# shield_motor.net
KiCad netlist of a schematic drawn in EAGLE
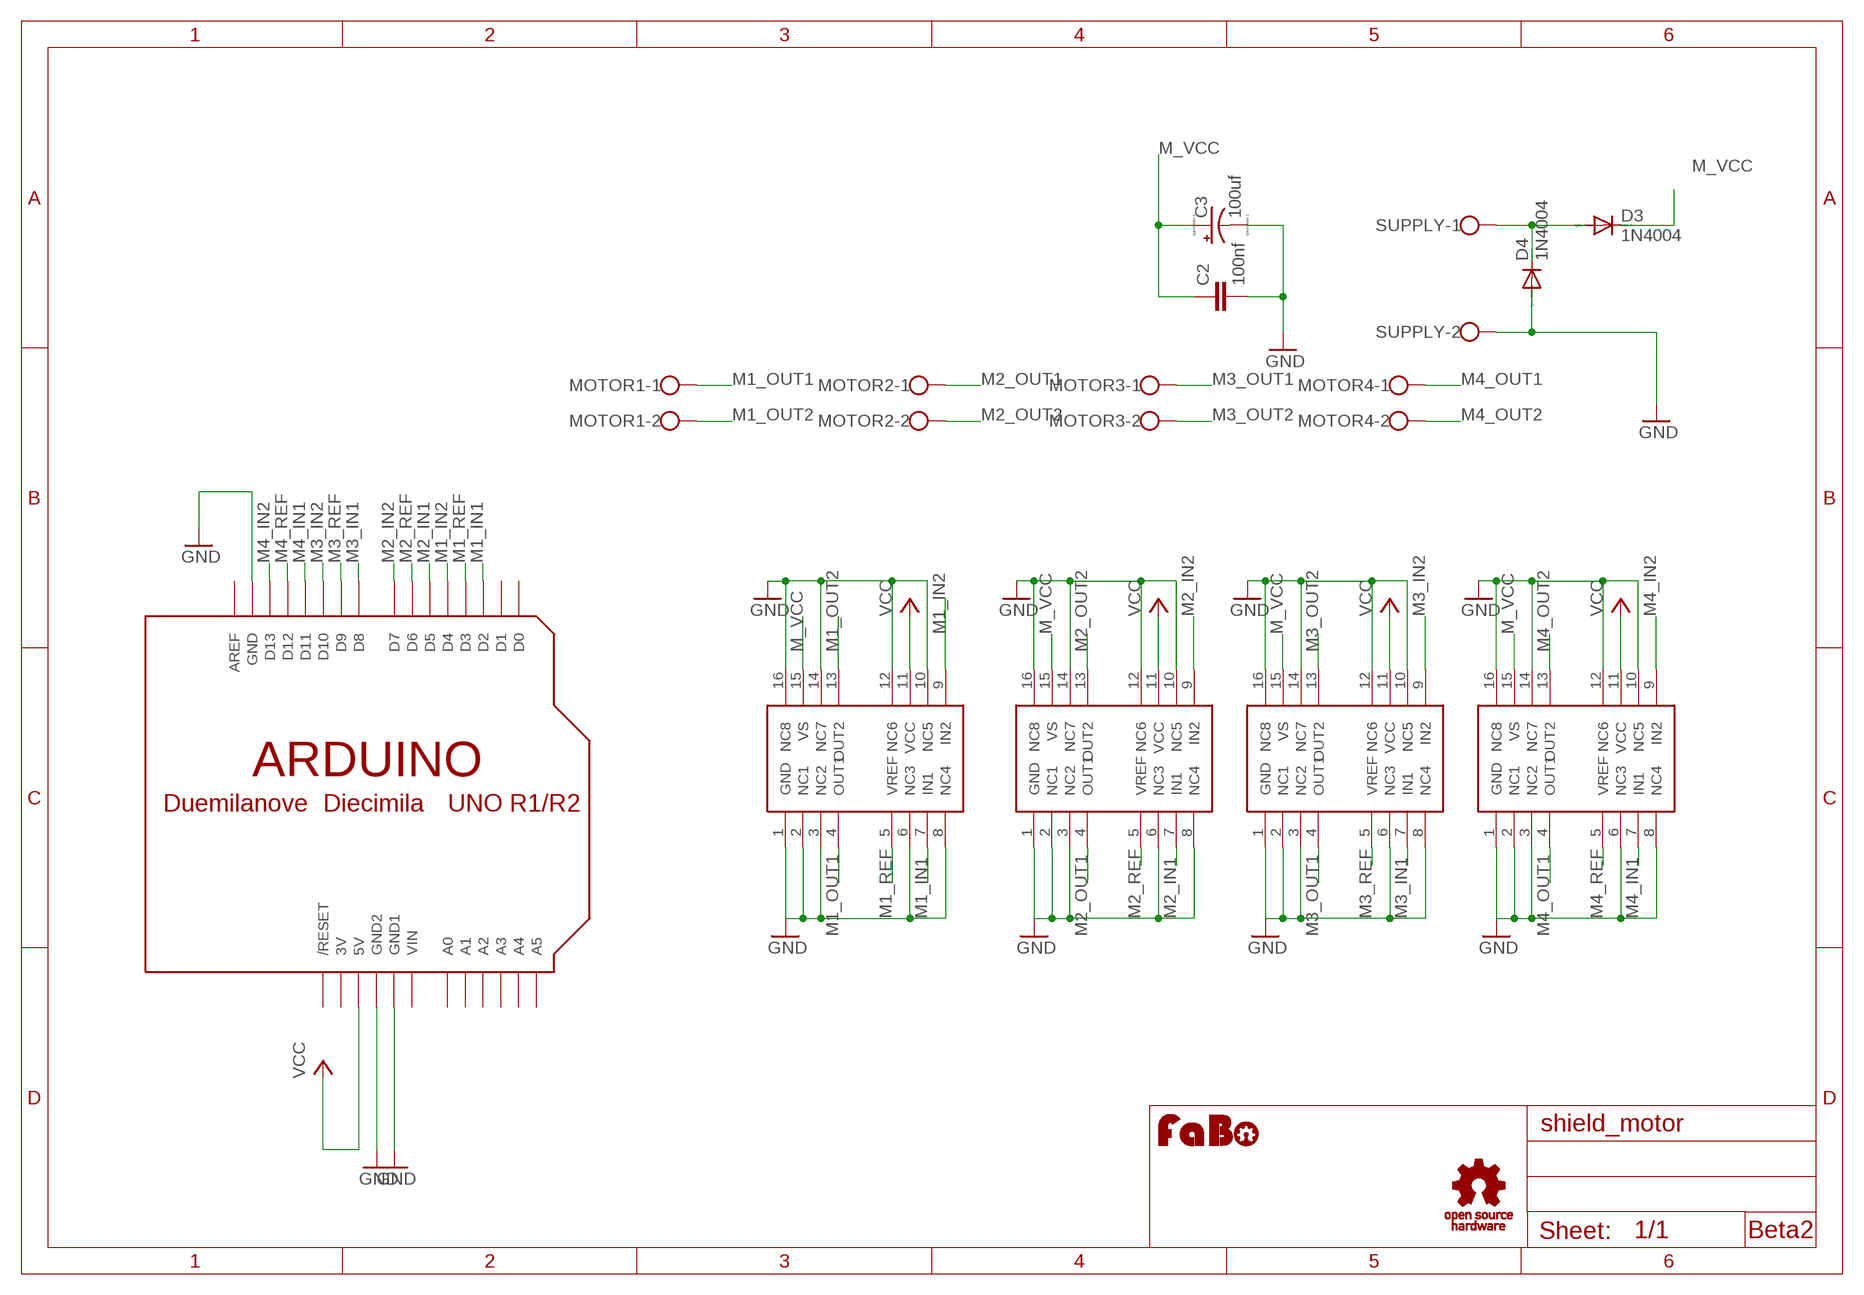
[diagram p0: schematic, sheet 1]

(export (version "E")
  (design (tool "Eeschema 10.0.6"))
  (components
    (comp (ref "C2")
      (value "100nf")
      (footprint "eagle-import:C0603")
      (libsource (lib "eagle-import") (part "C-EUC0603"))
    )
    (comp (ref "C3")
      (value "100uf")
      (footprint "eagle-import:153CLV-0405")
      (libsource (lib "eagle-import") (part "CPOL-US153CLV-0405"))
    )
    (comp (ref "D3")
      (value "1N4004")
      (footprint "eagle-import:DO41-10")
      (libsource (lib "eagle-import") (part "1N4004"))
    )
    (comp (ref "D4")
      (value "1N4004")
      (footprint "eagle-import:DO41-10")
      (libsource (lib "eagle-import") (part "1N4004"))
    )
    (comp (ref "MOTOR1")
      (value "W237-102")
      (footprint "eagle-import:W237-102")
      (fields (field (name "MPN") "237-102"))
      (libsource (lib "eagle-import") (part "W237-102"))
    )
    (comp (ref "MOTOR2")
      (value "W237-102")
      (footprint "eagle-import:W237-102")
      (fields (field (name "MPN") "237-102"))
      (libsource (lib "eagle-import") (part "W237-102"))
    )
    (comp (ref "MOTOR3")
      (value "W237-102")
      (footprint "eagle-import:W237-102")
      (fields (field (name "MPN") "237-102"))
      (libsource (lib "eagle-import") (part "W237-102"))
    )
    (comp (ref "MOTOR4")
      (value "W237-102")
      (footprint "eagle-import:W237-102")
      (fields (field (name "MPN") "237-102"))
      (libsource (lib "eagle-import") (part "W237-102"))
    )
    (comp (ref "SUPPLY")
      (value "W237-102")
      (footprint "eagle-import:W237-102")
      (fields (field (name "MPN") "237-102"))
      (libsource (lib "eagle-import") (part "W237-102"))
    )
    (comp (ref "U$1")
      (value "ARDUINO-NOHOLE")
      (footprint "eagle-import:ARDUINO-NOHOLE")
      (libsource (lib "eagle-import") (part "ARDUINO-NOHOLE"))
    )
    (comp (ref "U$2")
      (value "MOTOR-DRIVER-TA7281FG")
      (footprint "eagle-import:MOTOR-DRIVER-TA7291FG")
      (libsource (lib "eagle-import") (part "MOTOR-DRIVER-TA7281FG"))
    )
    (comp (ref "U$3")
      (value "MOTOR-DRIVER-TA7281FG")
      (footprint "eagle-import:MOTOR-DRIVER-TA7291FG")
      (libsource (lib "eagle-import") (part "MOTOR-DRIVER-TA7281FG"))
    )
    (comp (ref "U$4")
      (value "MOTOR-DRIVER-TA7281FG")
      (footprint "eagle-import:MOTOR-DRIVER-TA7291FG")
      (libsource (lib "eagle-import") (part "MOTOR-DRIVER-TA7281FG"))
    )
    (comp (ref "U$5")
      (value "MOTOR-DRIVER-TA7281FG")
      (footprint "eagle-import:MOTOR-DRIVER-TA7291FG")
      (libsource (lib "eagle-import") (part "MOTOR-DRIVER-TA7281FG"))
    )
    (comp (ref "U$7")
      (value "LOGO_FABO-M")
      (footprint "eagle-import:LOGO_FABO_M")
      (libsource (lib "eagle-import") (part "LOGO_FABO-M"))
    )
    (comp (ref "U$8")
      (value "LOGO_OSHW_T-M")
      (footprint "eagle-import:LOGO_OSHW_T_M")
      (libsource (lib "eagle-import") (part "LOGO_OSHW_T-M"))
    )
  )
  (nets
    (net (code "1") (name "/3V") (class "Default")
      (node (ref "U$1") (pin "3V") (pinfunction "3V_3V") (pintype "power_in"))
    )
    (net (code "2") (name "/M1_IN1") (class "Default")
      (node (ref "U$1") (pin "D2") (pinfunction "D2_D2") (pintype "bidirectional"))
      (node (ref "U$3") (pin "7") (pinfunction "IN1_7") (pintype "bidirectional"))
    )
    (net (code "3") (name "/M1_IN2") (class "Default")
      (node (ref "U$1") (pin "D4") (pinfunction "D4_D4") (pintype "bidirectional"))
      (node (ref "U$3") (pin "9") (pinfunction "IN2_9") (pintype "bidirectional"))
    )
    (net (code "4") (name "/M1_OUT1") (class "Default")
      (node (ref "MOTOR1") (pin "1") (pinfunction "KL_1") (pintype "passive"))
      (node (ref "U$3") (pin "4") (pinfunction "OUT1_4") (pintype "bidirectional"))
    )
    (net (code "5") (name "/M1_OUT2") (class "Default")
      (node (ref "MOTOR1") (pin "2") (pinfunction "KL_2") (pintype "passive"))
      (node (ref "U$3") (pin "13") (pinfunction "OUT2_13") (pintype "bidirectional"))
    )
    (net (code "6") (name "/M1_REF") (class "Default")
      (node (ref "U$1") (pin "D3") (pinfunction "D3_D3") (pintype "bidirectional"))
      (node (ref "U$3") (pin "5") (pinfunction "VREF_5") (pintype "bidirectional"))
    )
    (net (code "7") (name "/M2_IN1") (class "Default")
      (node (ref "U$1") (pin "D5") (pinfunction "D5_D5") (pintype "bidirectional"))
      (node (ref "U$4") (pin "7") (pinfunction "IN1_7") (pintype "bidirectional"))
    )
    (net (code "8") (name "/M2_IN2") (class "Default")
      (node (ref "U$1") (pin "D7") (pinfunction "D7_D7") (pintype "bidirectional"))
      (node (ref "U$4") (pin "9") (pinfunction "IN2_9") (pintype "bidirectional"))
    )
    (net (code "9") (name "/M2_OUT1") (class "Default")
      (node (ref "MOTOR2") (pin "1") (pinfunction "KL_1") (pintype "passive"))
      (node (ref "U$4") (pin "4") (pinfunction "OUT1_4") (pintype "bidirectional"))
    )
    (net (code "10") (name "/M2_OUT2") (class "Default")
      (node (ref "MOTOR2") (pin "2") (pinfunction "KL_2") (pintype "passive"))
      (node (ref "U$4") (pin "13") (pinfunction "OUT2_13") (pintype "bidirectional"))
    )
    (net (code "11") (name "/M2_REF") (class "Default")
      (node (ref "U$1") (pin "D6") (pinfunction "D6_D6") (pintype "bidirectional"))
      (node (ref "U$4") (pin "5") (pinfunction "VREF_5") (pintype "bidirectional"))
    )
    (net (code "12") (name "/M3_IN1") (class "Default")
      (node (ref "U$1") (pin "D8") (pinfunction "D8_D8") (pintype "bidirectional"))
      (node (ref "U$2") (pin "7") (pinfunction "IN1_7") (pintype "bidirectional"))
    )
    (net (code "13") (name "/M3_IN2") (class "Default")
      (node (ref "U$1") (pin "D10") (pinfunction "D10_D10") (pintype "bidirectional"))
      (node (ref "U$2") (pin "9") (pinfunction "IN2_9") (pintype "bidirectional"))
    )
    (net (code "14") (name "/M3_OUT1") (class "Default")
      (node (ref "MOTOR3") (pin "1") (pinfunction "KL_1") (pintype "passive"))
      (node (ref "U$2") (pin "4") (pinfunction "OUT1_4") (pintype "bidirectional"))
    )
    (net (code "15") (name "/M3_OUT2") (class "Default")
      (node (ref "MOTOR3") (pin "2") (pinfunction "KL_2") (pintype "passive"))
      (node (ref "U$2") (pin "13") (pinfunction "OUT2_13") (pintype "bidirectional"))
    )
    (net (code "16") (name "/M3_REF") (class "Default")
      (node (ref "U$1") (pin "D9") (pinfunction "D9_D9") (pintype "bidirectional"))
      (node (ref "U$2") (pin "5") (pinfunction "VREF_5") (pintype "bidirectional"))
    )
    (net (code "17") (name "/M4_IN1") (class "Default")
      (node (ref "U$1") (pin "D11") (pinfunction "D11_D11") (pintype "bidirectional"))
      (node (ref "U$5") (pin "7") (pinfunction "IN1_7") (pintype "bidirectional"))
    )
    (net (code "18") (name "/M4_IN2") (class "Default")
      (node (ref "U$1") (pin "D13") (pinfunction "D13_D13") (pintype "bidirectional"))
      (node (ref "U$5") (pin "9") (pinfunction "IN2_9") (pintype "bidirectional"))
    )
    (net (code "19") (name "/M4_OUT1") (class "Default")
      (node (ref "MOTOR4") (pin "1") (pinfunction "KL_1") (pintype "passive"))
      (node (ref "U$5") (pin "4") (pinfunction "OUT1_4") (pintype "bidirectional"))
    )
    (net (code "20") (name "/M4_OUT2") (class "Default")
      (node (ref "MOTOR4") (pin "2") (pinfunction "KL_2") (pintype "passive"))
      (node (ref "U$5") (pin "13") (pinfunction "OUT2_13") (pintype "bidirectional"))
    )
    (net (code "21") (name "/M4_REF") (class "Default")
      (node (ref "U$1") (pin "D12") (pinfunction "D12_D12") (pintype "bidirectional"))
      (node (ref "U$5") (pin "5") (pinfunction "VREF_5") (pintype "bidirectional"))
    )
    (net (code "22") (name "/M_VCC") (class "Default")
      (node (ref "C2") (pin "1") (pinfunction "1_1") (pintype "passive"))
      (node (ref "C3") (pin "+") (pinfunction "+_+") (pintype "passive"))
      (node (ref "D3") (pin "C") (pinfunction "C_C") (pintype "passive"))
      (node (ref "U$2") (pin "15") (pinfunction "VS_15") (pintype "bidirectional"))
      (node (ref "U$3") (pin "15") (pinfunction "VS_15") (pintype "bidirectional"))
      (node (ref "U$4") (pin "15") (pinfunction "VS_15") (pintype "bidirectional"))
      (node (ref "U$5") (pin "15") (pinfunction "VS_15") (pintype "bidirectional"))
    )
    (net (code "23") (name "/VIN") (class "Default")
      (node (ref "U$1") (pin "VIN") (pinfunction "VIN_VIN") (pintype "power_in"))
    )
    (net (code "24") (name "GND") (class "Default")
      (node (ref "C2") (pin "2") (pinfunction "2_2") (pintype "passive"))
      (node (ref "C3") (pin "-") (pinfunction "-_-") (pintype "passive"))
      (node (ref "D4") (pin "A") (pinfunction "A_A") (pintype "passive"))
      (node (ref "SUPPLY") (pin "2") (pinfunction "KL_2") (pintype "passive"))
      (node (ref "U$1") (pin "GND") (pinfunction "GND_GND") (pintype "power_in"))
      (node (ref "U$1") (pin "GND1") (pinfunction "GND1_GND1") (pintype "power_in"))
      (node (ref "U$1") (pin "GND2") (pinfunction "GND2_GND2") (pintype "power_in"))
      (node (ref "U$2") (pin "1") (pinfunction "GND_1") (pintype "bidirectional"))
      (node (ref "U$2") (pin "10") (pinfunction "NC5_10") (pintype "bidirectional"))
      (node (ref "U$2") (pin "12") (pinfunction "NC6_12") (pintype "bidirectional"))
      (node (ref "U$2") (pin "14") (pinfunction "NC7_14") (pintype "bidirectional"))
      (node (ref "U$2") (pin "16") (pinfunction "NC8_16") (pintype "bidirectional"))
      (node (ref "U$2") (pin "2") (pinfunction "NC1_2") (pintype "bidirectional"))
      (node (ref "U$2") (pin "3") (pinfunction "NC2_3") (pintype "bidirectional"))
      (node (ref "U$2") (pin "6") (pinfunction "NC3_6") (pintype "bidirectional"))
      (node (ref "U$2") (pin "8") (pinfunction "NC4_8") (pintype "bidirectional"))
      (node (ref "U$3") (pin "1") (pinfunction "GND_1") (pintype "bidirectional"))
      (node (ref "U$3") (pin "10") (pinfunction "NC5_10") (pintype "bidirectional"))
      (node (ref "U$3") (pin "12") (pinfunction "NC6_12") (pintype "bidirectional"))
      (node (ref "U$3") (pin "14") (pinfunction "NC7_14") (pintype "bidirectional"))
      (node (ref "U$3") (pin "16") (pinfunction "NC8_16") (pintype "bidirectional"))
      (node (ref "U$3") (pin "2") (pinfunction "NC1_2") (pintype "bidirectional"))
      (node (ref "U$3") (pin "3") (pinfunction "NC2_3") (pintype "bidirectional"))
      (node (ref "U$3") (pin "6") (pinfunction "NC3_6") (pintype "bidirectional"))
      (node (ref "U$3") (pin "8") (pinfunction "NC4_8") (pintype "bidirectional"))
      (node (ref "U$4") (pin "1") (pinfunction "GND_1") (pintype "bidirectional"))
      (node (ref "U$4") (pin "10") (pinfunction "NC5_10") (pintype "bidirectional"))
      (node (ref "U$4") (pin "12") (pinfunction "NC6_12") (pintype "bidirectional"))
      (node (ref "U$4") (pin "14") (pinfunction "NC7_14") (pintype "bidirectional"))
      (node (ref "U$4") (pin "16") (pinfunction "NC8_16") (pintype "bidirectional"))
      (node (ref "U$4") (pin "2") (pinfunction "NC1_2") (pintype "bidirectional"))
      (node (ref "U$4") (pin "3") (pinfunction "NC2_3") (pintype "bidirectional"))
      (node (ref "U$4") (pin "6") (pinfunction "NC3_6") (pintype "bidirectional"))
      (node (ref "U$4") (pin "8") (pinfunction "NC4_8") (pintype "bidirectional"))
      (node (ref "U$5") (pin "1") (pinfunction "GND_1") (pintype "bidirectional"))
      (node (ref "U$5") (pin "10") (pinfunction "NC5_10") (pintype "bidirectional"))
      (node (ref "U$5") (pin "12") (pinfunction "NC6_12") (pintype "bidirectional"))
      (node (ref "U$5") (pin "14") (pinfunction "NC7_14") (pintype "bidirectional"))
      (node (ref "U$5") (pin "16") (pinfunction "NC8_16") (pintype "bidirectional"))
      (node (ref "U$5") (pin "2") (pinfunction "NC1_2") (pintype "bidirectional"))
      (node (ref "U$5") (pin "3") (pinfunction "NC2_3") (pintype "bidirectional"))
      (node (ref "U$5") (pin "6") (pinfunction "NC3_6") (pintype "bidirectional"))
      (node (ref "U$5") (pin "8") (pinfunction "NC4_8") (pintype "bidirectional"))
    )
    (net (code "25") (name "Net-(SUPPLYA-KL)") (class "Default")
      (node (ref "D3") (pin "A") (pinfunction "A_A") (pintype "passive"))
      (node (ref "D4") (pin "C") (pinfunction "C_C") (pintype "passive"))
      (node (ref "SUPPLY") (pin "1") (pinfunction "KL_1") (pintype "passive"))
    )
    (net (code "26") (name "VCC") (class "Default")
      (node (ref "U$1") (pin "5V") (pinfunction "5V_5V") (pintype "power_in"))
      (node (ref "U$2") (pin "11") (pinfunction "VCC_11") (pintype "bidirectional"))
      (node (ref "U$3") (pin "11") (pinfunction "VCC_11") (pintype "bidirectional"))
      (node (ref "U$4") (pin "11") (pinfunction "VCC_11") (pintype "bidirectional"))
      (node (ref "U$5") (pin "11") (pinfunction "VCC_11") (pintype "bidirectional"))
    )
    (net (code "27") (name "unconnected-(U$1-PadA0)") (class "Default")
      (node (ref "U$1") (pin "A0") (pinfunction "A0_A0") (pintype "bidirectional"))
    )
    (net (code "28") (name "unconnected-(U$1-PadA1)") (class "Default")
      (node (ref "U$1") (pin "A1") (pinfunction "A1_A1") (pintype "bidirectional"))
    )
    (net (code "29") (name "unconnected-(U$1-PadA2)") (class "Default")
      (node (ref "U$1") (pin "A2") (pinfunction "A2_A2") (pintype "bidirectional"))
    )
    (net (code "30") (name "unconnected-(U$1-PadA3)") (class "Default")
      (node (ref "U$1") (pin "A3") (pinfunction "A3_A3") (pintype "bidirectional"))
    )
    (net (code "31") (name "unconnected-(U$1-PadA4)") (class "Default")
      (node (ref "U$1") (pin "A4") (pinfunction "A4_A4") (pintype "bidirectional"))
    )
    (net (code "32") (name "unconnected-(U$1-PadA5)") (class "Default")
      (node (ref "U$1") (pin "A5") (pinfunction "A5_A5") (pintype "bidirectional"))
    )
    (net (code "33") (name "unconnected-(U$1-PadAREF)") (class "Default")
      (node (ref "U$1") (pin "AREF") (pinfunction "AREF_AREF") (pintype "bidirectional"))
    )
    (net (code "34") (name "unconnected-(U$1-PadD0)") (class "Default")
      (node (ref "U$1") (pin "D0") (pinfunction "D0_D0") (pintype "bidirectional"))
    )
    (net (code "35") (name "unconnected-(U$1-PadD1)") (class "Default")
      (node (ref "U$1") (pin "D1") (pinfunction "D1_D1") (pintype "bidirectional"))
    )
    (net (code "36") (name "unconnected-(U$1-{slash}RESET-PadRESET)") (class "Default")
      (node (ref "U$1") (pin "RESET") (pinfunction "/RESET_RESET") (pintype "bidirectional"))
    )
  )
)
